# IO_Connectors.net
KiCad netlist of a schematic drawn in Altium Designer
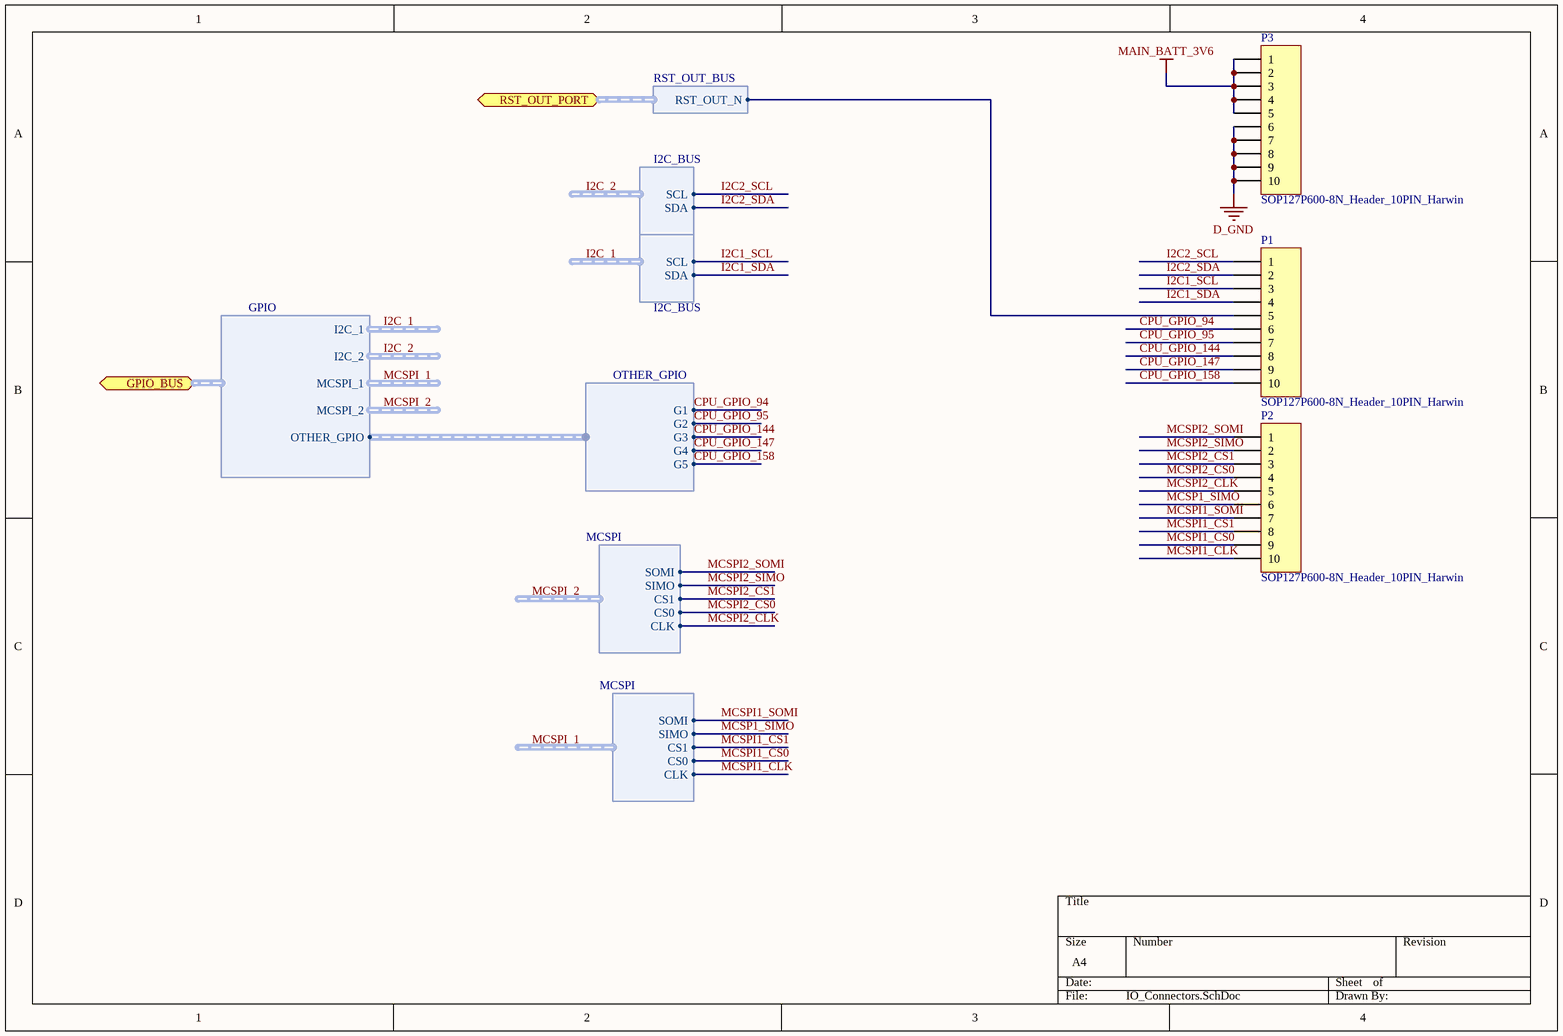
[diagram p0: IO_Connectors.SchDoc]

(export (version "E")
  (design (tool "Eeschema 10.0.6"))
  (components
    (comp (ref "P1")
      (value "SOP127P600-8N_Header_10PIN_Harwin")
      (footprint "SOP127P600-8N_Header_10PIN_Harwin:SOP127P600-8N_Header_10PIN_Harwin")
      (description "Header, 10-Pin")
      (fields (field (name "PUBLISHER") "Altium Limited"))
      (libsource (lib "Miscellaneous Connectors") (part "Header 10"))
    )
    (comp (ref "P2")
      (value "SOP127P600-8N_Header_10PIN_Harwin")
      (footprint "SOP127P600-8N_Header_10PIN_Harwin:SOP127P600-8N_Header_10PIN_Harwin")
      (description "Header, 10-Pin")
      (fields (field (name "PUBLISHER") "Altium Limited"))
      (libsource (lib "Miscellaneous Connectors") (part "Header 10"))
    )
    (comp (ref "P3")
      (value "SOP127P600-8N_Header_10PIN_Harwin")
      (footprint "SOP127P600-8N_Header_10PIN_Harwin:SOP127P600-8N_Header_10PIN_Harwin")
      (description "Header, 10-Pin")
      (fields (field (name "PUBLISHER") "Altium Limited"))
      (libsource (lib "Miscellaneous Connectors") (part "Header 10"))
    )
  )
  (nets
    (net (code "12") (name "/CPU_GPIO_94") (class "Default")
      (node (ref "P1") (pin "6") (pinfunction "6_6") (pintype "passive"))
    )
    (net (code "13") (name "/CPU_GPIO_95") (class "Default")
      (node (ref "P1") (pin "7") (pinfunction "7_7") (pintype "passive"))
    )
    (net (code "14") (name "/CPU_GPIO_144") (class "Default")
      (node (ref "P1") (pin "8") (pinfunction "8_8") (pintype "passive"))
    )
    (net (code "15") (name "/CPU_GPIO_147") (class "Default")
      (node (ref "P1") (pin "9") (pinfunction "9_9") (pintype "passive"))
    )
    (net (code "16") (name "/CPU_GPIO_158") (class "Default")
      (node (ref "P1") (pin "10") (pinfunction "10_10") (pintype "passive"))
    )
    (net (code "18") (name "/I2C1_SCL") (class "Default")
      (node (ref "P1") (pin "3") (pinfunction "3_3") (pintype "passive"))
    )
    (net (code "19") (name "/I2C1_SDA") (class "Default")
      (node (ref "P1") (pin "4") (pinfunction "4_4") (pintype "passive"))
    )
    (net (code "20") (name "/I2C2_SCL") (class "Default")
      (node (ref "P1") (pin "1") (pinfunction "1_1") (pintype "passive"))
    )
    (net (code "21") (name "/I2C2_SDA") (class "Default")
      (node (ref "P1") (pin "2") (pinfunction "2_2") (pintype "passive"))
    )
    (net (code "24") (name "/MCSP1_SIMO") (class "Default")
      (node (ref "P2") (pin "6") (pinfunction "6_6") (pintype "passive"))
    )
    (net (code "25") (name "/MCSPI1_CLK") (class "Default")
      (node (ref "P2") (pin "10") (pinfunction "10_10") (pintype "passive"))
    )
    (net (code "26") (name "/MCSPI1_CS0") (class "Default")
      (node (ref "P2") (pin "9") (pinfunction "9_9") (pintype "passive"))
    )
    (net (code "27") (name "/MCSPI1_CS1") (class "Default")
      (node (ref "P2") (pin "8") (pinfunction "8_8") (pintype "passive"))
    )
    (net (code "28") (name "/MCSPI1_SOMI") (class "Default")
      (node (ref "P2") (pin "7") (pinfunction "7_7") (pintype "passive"))
    )
    (net (code "29") (name "/MCSPI2_CLK") (class "Default")
      (node (ref "P2") (pin "5") (pinfunction "5_5") (pintype "passive"))
    )
    (net (code "30") (name "/MCSPI2_CS0") (class "Default")
      (node (ref "P2") (pin "4") (pinfunction "4_4") (pintype "passive"))
    )
    (net (code "31") (name "/MCSPI2_CS1") (class "Default")
      (node (ref "P2") (pin "3") (pinfunction "3_3") (pintype "passive"))
    )
    (net (code "32") (name "/MCSPI2_SIMO") (class "Default")
      (node (ref "P2") (pin "2") (pinfunction "2_2") (pintype "passive"))
    )
    (net (code "33") (name "/MCSPI2_SOMI") (class "Default")
      (node (ref "P2") (pin "1") (pinfunction "1_1") (pintype "passive"))
    )
    (net (code "36") (name "/RST_OUT_N") (class "Default")
      (node (ref "P1") (pin "5") (pinfunction "5_5") (pintype "passive"))
    )
    (net (code "43") (name "D_GND") (class "Default")
      (node (ref "P3") (pin "10") (pinfunction "10_10") (pintype "passive"))
      (node (ref "P3") (pin "6") (pinfunction "6_6") (pintype "passive"))
      (node (ref "P3") (pin "7") (pinfunction "7_7") (pintype "passive"))
      (node (ref "P3") (pin "8") (pinfunction "8_8") (pintype "passive"))
      (node (ref "P3") (pin "9") (pinfunction "9_9") (pintype "passive"))
    )
    (net (code "44") (name "MAIN_BATT_3V6") (class "Default")
      (node (ref "P3") (pin "1") (pinfunction "1_1") (pintype "passive"))
      (node (ref "P3") (pin "2") (pinfunction "2_2") (pintype "passive"))
      (node (ref "P3") (pin "3") (pinfunction "3_3") (pintype "passive"))
      (node (ref "P3") (pin "4") (pinfunction "4_4") (pintype "passive"))
      (node (ref "P3") (pin "5") (pinfunction "5_5") (pintype "passive"))
    )
  )
)
